# SCH_Arduino-Programmer_2024-08-11.net
KiCad netlist of a schematic drawn in EasyEDA
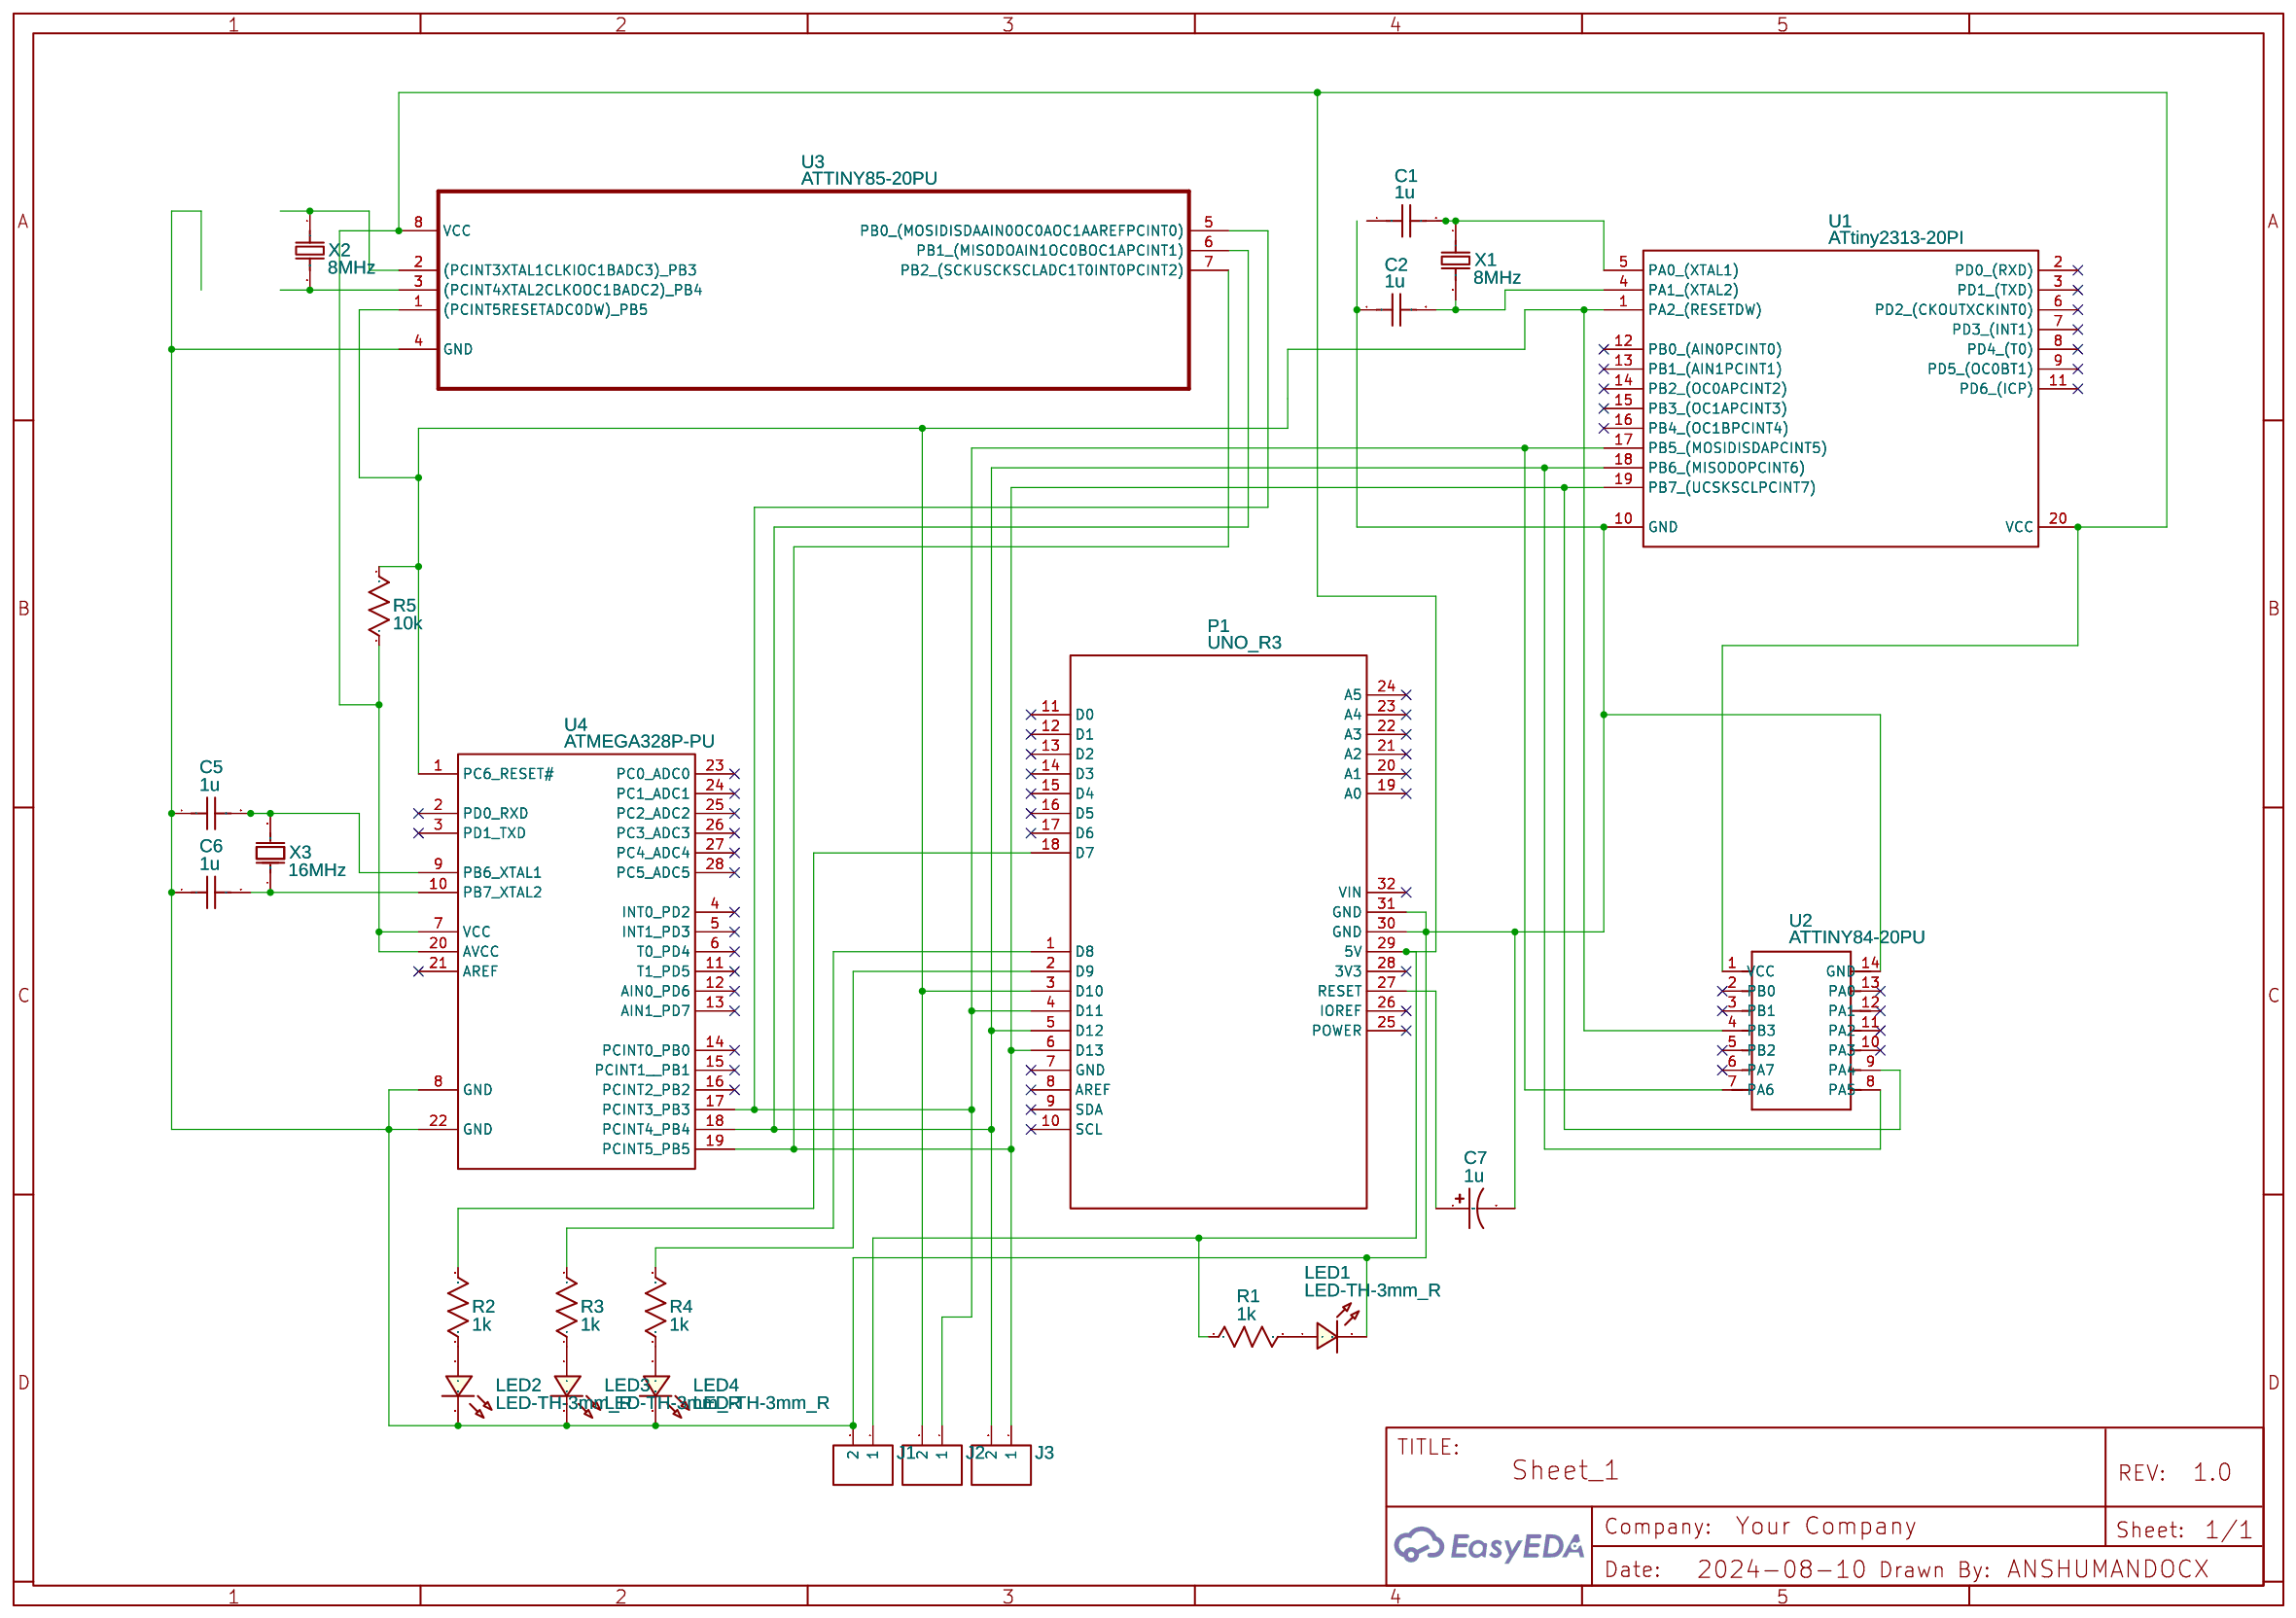
[diagram p0: schematic sheet]

(export (version "E")
  (design (tool "Eeschema 10.0.6"))
  (components
    (comp (ref "C1") (value "1u") (libsource (lib "") (part "C_RAD-0.1_US")))
    (comp (ref "C2") (value "1u") (libsource (lib "") (part "C_RAD-0.1_US")))
    (comp (ref "C5") (value "1u") (libsource (lib "") (part "C_RAD-0.1_US")))
    (comp (ref "C6") (value "1u") (libsource (lib "") (part "C_RAD-0.1_US")))
    (comp (ref "C7") (value "1u") (libsource (lib "") (part "CE_TH_D5.0×F2.0_US")))
    (comp (ref "J1") (value "HDR-M-2.54_1x2") (libsource (lib "") (part "HDR-M-2.54_1x2")))
    (comp (ref "J2") (value "HDR-M-2.54_1x2") (libsource (lib "") (part "HDR-M-2.54_1x2")))
    (comp (ref "J3") (value "HDR-M-2.54_1x2") (libsource (lib "") (part "HDR-M-2.54_1x2")))
    (comp (ref "LED1")
      (value "LED-TH-3mm_R")
      (fields
        (field (name "Manufacturer Part") "204-10SDRD/S530-A3-L")
        (field (name "Manufacturer") "EVERLIGHT(台湾亿光)")
      )
      (libsource (lib "") (part "LED-TH-3mm_R_1"))
    )
    (comp (ref "LED2")
      (value "LED-TH-3mm_R")
      (fields
        (field (name "Manufacturer Part") "204-10SDRD/S530-A3-L")
        (field (name "Manufacturer") "EVERLIGHT(台湾亿光)")
      )
      (libsource (lib "") (part "LED-TH-3mm_R"))
    )
    (comp (ref "LED3")
      (value "LED-TH-3mm_R")
      (fields
        (field (name "Manufacturer Part") "204-10SDRD/S530-A3-L")
        (field (name "Manufacturer") "EVERLIGHT(台湾亿光)")
      )
      (libsource (lib "") (part "LED-TH-3mm_R"))
    )
    (comp (ref "LED4")
      (value "LED-TH-3mm_R")
      (fields
        (field (name "Manufacturer Part") "204-10SDRD/S530-A3-L")
        (field (name "Manufacturer") "EVERLIGHT(台湾亿光)")
      )
      (libsource (lib "") (part "LED-TH-3mm_R"))
    )
    (comp (ref "P1") (value "UNO_R3") (libsource (lib "") (part "UNO_R3")))
    (comp (ref "R1") (value "1k") (libsource (lib "") (part "R_AXIAL-0.4_US")))
    (comp (ref "R2") (value "1k") (libsource (lib "") (part "R_AXIAL-0.4_US_1")))
    (comp (ref "R3") (value "1k") (libsource (lib "") (part "R_AXIAL-0.4_US_1")))
    (comp (ref "R4") (value "1k") (libsource (lib "") (part "R_AXIAL-0.4_US_1")))
    (comp (ref "R5") (value "10k") (libsource (lib "") (part "R_AXIAL-0.4_US_1")))
    (comp (ref "U1") (value "ATtiny2313-20PI") (libsource (lib "") (part "ATtiny2313-20PI")))
    (comp (ref "U2") (value "ATTINY84-20PU") (libsource (lib "") (part "ATTINY84-20PU")))
    (comp (ref "U3") (value "ATTINY85-20PU") (libsource (lib "") (part "ATTINY85-20PU")))
    (comp (ref "U4")
      (value "ATMEGA328P-PU")
      (fields (field (name "Manufacturer") "MICROCHIP(美国微芯)"))
      (libsource (lib "") (part "ATMEGA328P-PU"))
    )
    (comp (ref "X1")
      (value "8MHz")
      (fields (field (name "Manufacturer Part") "9B08000006") (field (name "Manufacturer") "TXC(晶技)"))
      (libsource (lib "") (part "9B0806LCSC-AHQ2S"))
    )
    (comp (ref "X2")
      (value "8MHz")
      (fields (field (name "Manufacturer Part") "9B08000006") (field (name "Manufacturer") "TXC(晶技)"))
      (libsource (lib "") (part "9B0806LCSC-AHQ2S"))
    )
    (comp (ref "X3")
      (value "16MHz")
      (fields
        (field (name "Manufacturer Part") "E49A16E00000DE10C0")
        (field (name "Manufacturer") "HOSONIC(鸿星)")
      )
      (libsource (lib "") (part "E49A16E00000DE10C0"))
    )
  )
  (nets
    (net (code "1") (name "Net-(LED1-Pad1)") (class "Default")
      (node (ref "LED1") (pin "1") (pinfunction "1_1") (pintype "unspecified"))
      (node (ref "R1") (pin "2") (pinfunction "2_2") (pintype "unspecified"))
    )
    (net (code "2") (name "Net-(LED2-Pad1)") (class "Default")
      (node (ref "LED2") (pin "1") (pinfunction "1_1") (pintype "unspecified"))
      (node (ref "R2") (pin "1") (pinfunction "1_1") (pintype "unspecified"))
    )
    (net (code "3") (name "Net-(LED3-Pad1)") (class "Default")
      (node (ref "LED3") (pin "1") (pinfunction "1_1") (pintype "unspecified"))
      (node (ref "R3") (pin "1") (pinfunction "1_1") (pintype "unspecified"))
    )
    (net (code "4") (name "Net-(LED4-Pad1)") (class "Default")
      (node (ref "LED4") (pin "1") (pinfunction "1_1") (pintype "unspecified"))
      (node (ref "R4") (pin "1") (pinfunction "1_1") (pintype "unspecified"))
    )
    (net (code "5") (name "Net-(P1-5V)") (class "Default")
      (node (ref "J1") (pin "1") (pinfunction "1_1") (pintype "unspecified"))
      (node (ref "P1") (pin "29") (pinfunction "5V_29") (pintype "unspecified"))
      (node (ref "R1") (pin "1") (pinfunction "1_1") (pintype "unspecified"))
      (node (ref "R5") (pin "1") (pinfunction "1_1") (pintype "unspecified"))
      (node (ref "U1") (pin "20") (pinfunction "VCC_20") (pintype "passive"))
      (node (ref "U2") (pin "1") (pinfunction "VCC_1") (pintype "unspecified"))
      (node (ref "U3") (pin "8") (pinfunction "VCC_8") (pintype "passive"))
      (node (ref "U4") (pin "20") (pinfunction "AVCC_20") (pintype "passive"))
      (node (ref "U4") (pin "7") (pinfunction "VCC_7") (pintype "passive"))
    )
    (net (code "6") (name "Net-(P1-D7)") (class "Default")
      (node (ref "P1") (pin "18") (pinfunction "D7_18") (pintype "unspecified"))
      (node (ref "R2") (pin "2") (pinfunction "2_2") (pintype "unspecified"))
    )
    (net (code "7") (name "Net-(P1-D8)") (class "Default")
      (node (ref "P1") (pin "1") (pinfunction "D8_1") (pintype "unspecified"))
      (node (ref "R3") (pin "2") (pinfunction "2_2") (pintype "unspecified"))
    )
    (net (code "8") (name "Net-(P1-D9)") (class "Default")
      (node (ref "P1") (pin "2") (pinfunction "D9_2") (pintype "unspecified"))
      (node (ref "R4") (pin "2") (pinfunction "2_2") (pintype "unspecified"))
    )
    (net (code "9") (name "Net-(P1-D10)") (class "Default")
      (node (ref "J2") (pin "2") (pinfunction "2_2") (pintype "unspecified"))
      (node (ref "P1") (pin "3") (pinfunction "D10_3") (pintype "unspecified"))
      (node (ref "R5") (pin "2") (pinfunction "2_2") (pintype "unspecified"))
      (node (ref "U1") (pin "1") (pinfunction "PA2_(RESETDW)_1") (pintype "bidirectional"))
      (node (ref "U2") (pin "4") (pinfunction "PB3_4") (pintype "unspecified"))
      (node (ref "U3") (pin "1") (pinfunction "(PCINT5RESETADC0DW)_PB5_1") (pintype "unspecified"))
      (node (ref "U4") (pin "1") (pinfunction "PC6_RESET#_1") (pintype "bidirectional"))
    )
    (net (code "10") (name "Net-(P1-D11)") (class "Default")
      (node (ref "J2") (pin "1") (pinfunction "1_1") (pintype "unspecified"))
      (node (ref "P1") (pin "4") (pinfunction "D11_4") (pintype "unspecified"))
      (node (ref "U1") (pin "17") (pinfunction "PB5_(MOSIDISDAPCINT5)_17") (pintype "bidirectional"))
      (node (ref "U2") (pin "7") (pinfunction "PA6_7") (pintype "unspecified"))
      (node (ref "U3") (pin "5") (pinfunction "PB0_(MOSIDISDAAIN0OC0AOC1AAREFPCINT0)_5") (pintype "unspecified"))
      (node (ref "U4") (pin "17") (pinfunction "PCINT3_PB3_17") (pintype "bidirectional"))
    )
    (net (code "11") (name "Net-(P1-D12)") (class "Default")
      (node (ref "J3") (pin "2") (pinfunction "2_2") (pintype "unspecified"))
      (node (ref "P1") (pin "5") (pinfunction "D12_5") (pintype "unspecified"))
      (node (ref "U1") (pin "18") (pinfunction "PB6_(MISODOPCINT6)_18") (pintype "bidirectional"))
      (node (ref "U2") (pin "8") (pinfunction "PA5_8") (pintype "unspecified"))
      (node (ref "U3") (pin "6") (pinfunction "PB1_(MISODOAIN1OC0BOC1APCINT1)_6") (pintype "unspecified"))
      (node (ref "U4") (pin "18") (pinfunction "PCINT4_PB4_18") (pintype "bidirectional"))
    )
    (net (code "12") (name "Net-(P1-D13)") (class "Default")
      (node (ref "J3") (pin "1") (pinfunction "1_1") (pintype "unspecified"))
      (node (ref "P1") (pin "6") (pinfunction "D13_6") (pintype "unspecified"))
      (node (ref "U1") (pin "19") (pinfunction "PB7_(UCSKSCLPCINT7)_19") (pintype "bidirectional"))
      (node (ref "U2") (pin "9") (pinfunction "PA4_9") (pintype "unspecified"))
      (node (ref "U3") (pin "7") (pinfunction "PB2_(SCKUSCKSCLADC1T0INT0PCINT2)_7") (pintype "unspecified"))
      (node (ref "U4") (pin "19") (pinfunction "PCINT5_PB5_19") (pintype "bidirectional"))
    )
    (net (code "13") (name "Net-(P1-RESET)") (class "Default")
      (node (ref "C7") (pin "1") (pinfunction "1_1") (pintype "unspecified"))
      (node (ref "P1") (pin "27") (pinfunction "RESET_27") (pintype "unspecified"))
    )
    (net (code "14") (name "Net-(U1-GND)") (class "Default")
      (node (ref "C2") (pin "1") (pinfunction "1_1") (pintype "unspecified"))
      (node (ref "C5") (pin "1") (pinfunction "1_1") (pintype "unspecified"))
      (node (ref "C6") (pin "1") (pinfunction "1_1") (pintype "unspecified"))
      (node (ref "C7") (pin "2") (pinfunction "2_2") (pintype "unspecified"))
      (node (ref "J1") (pin "2") (pinfunction "2_2") (pintype "unspecified"))
      (node (ref "LED1") (pin "2") (pinfunction "2_2") (pintype "unspecified"))
      (node (ref "LED2") (pin "2") (pinfunction "2_2") (pintype "unspecified"))
      (node (ref "LED3") (pin "2") (pinfunction "2_2") (pintype "unspecified"))
      (node (ref "LED4") (pin "2") (pinfunction "2_2") (pintype "unspecified"))
      (node (ref "P1") (pin "30") (pinfunction "GND_30") (pintype "unspecified"))
      (node (ref "P1") (pin "31") (pinfunction "GND_31") (pintype "unspecified"))
      (node (ref "U1") (pin "10") (pinfunction "GND_10") (pintype "passive"))
      (node (ref "U2") (pin "14") (pinfunction "GND_14") (pintype "unspecified"))
      (node (ref "U3") (pin "4") (pinfunction "GND_4") (pintype "unspecified"))
      (node (ref "U4") (pin "22") (pinfunction "GND_22") (pintype "passive"))
      (node (ref "U4") (pin "8") (pinfunction "GND_8") (pintype "passive"))
    )
    (net (code "15") (name "Net-(U1-PA0_(XTAL1))") (class "Default")
      (node (ref "C1") (pin "2") (pinfunction "2_2") (pintype "unspecified"))
      (node (ref "U1") (pin "5") (pinfunction "PA0_(XTAL1)_5") (pintype "bidirectional"))
      (node (ref "X1") (pin "1") (pinfunction "1_1") (pintype "unspecified"))
    )
    (net (code "16") (name "Net-(U1-PA1_(XTAL2))") (class "Default")
      (node (ref "C2") (pin "2") (pinfunction "2_2") (pintype "unspecified"))
      (node (ref "U1") (pin "4") (pinfunction "PA1_(XTAL2)_4") (pintype "bidirectional"))
      (node (ref "X1") (pin "2") (pinfunction "2_2") (pintype "unspecified"))
    )
    (net (code "17") (name "Net-(U3-(PCINT3XTAL1CLKIOC1BADC3)_PB3)") (class "Default")
      (node (ref "U3") (pin "2") (pinfunction "(PCINT3XTAL1CLKIOC1BADC3)_PB3_2") (pintype "unspecified"))
      (node (ref "X2") (pin "1") (pinfunction "1_1") (pintype "unspecified"))
    )
    (net (code "18") (name "Net-(U3-(PCINT4XTAL2CLKOOC1BADC2)_PB4)") (class "Default")
      (node (ref "U3") (pin "3") (pinfunction "(PCINT4XTAL2CLKOOC1BADC2)_PB4_3") (pintype "unspecified"))
      (node (ref "X2") (pin "2") (pinfunction "2_2") (pintype "unspecified"))
    )
    (net (code "19") (name "Net-(U4-PB6_XTAL1)") (class "Default")
      (node (ref "C5") (pin "2") (pinfunction "2_2") (pintype "unspecified"))
      (node (ref "U4") (pin "9") (pinfunction "PB6_XTAL1_9") (pintype "bidirectional"))
      (node (ref "X3") (pin "2") (pinfunction "OSC2_2") (pintype "input"))
    )
    (net (code "20") (name "Net-(U4-PB7_XTAL2)") (class "Default")
      (node (ref "C6") (pin "2") (pinfunction "2_2") (pintype "unspecified"))
      (node (ref "U4") (pin "10") (pinfunction "PB7_XTAL2_10") (pintype "bidirectional"))
      (node (ref "X3") (pin "1") (pinfunction "OSC1_1") (pintype "input"))
    )
    (net (code "21") (name "unconnected-(C1-Pad1)") (class "Default")
      (node (ref "C1") (pin "1") (pinfunction "1_1") (pintype "unspecified"))
    )
    (net (code "22") (name "unconnected-(P1-3V3-Pad28)") (class "Default")
      (node (ref "P1") (pin "28") (pinfunction "3V3_28") (pintype "unspecified+no_connect"))
    )
    (net (code "23") (name "unconnected-(P1-A0-Pad19)") (class "Default")
      (node (ref "P1") (pin "19") (pinfunction "A0_19") (pintype "unspecified+no_connect"))
    )
    (net (code "24") (name "unconnected-(P1-A1-Pad20)") (class "Default")
      (node (ref "P1") (pin "20") (pinfunction "A1_20") (pintype "unspecified+no_connect"))
    )
    (net (code "25") (name "unconnected-(P1-A2-Pad21)") (class "Default")
      (node (ref "P1") (pin "21") (pinfunction "A2_21") (pintype "unspecified+no_connect"))
    )
    (net (code "26") (name "unconnected-(P1-A3-Pad22)") (class "Default")
      (node (ref "P1") (pin "22") (pinfunction "A3_22") (pintype "unspecified+no_connect"))
    )
    (net (code "27") (name "unconnected-(P1-A4-Pad23)") (class "Default")
      (node (ref "P1") (pin "23") (pinfunction "A4_23") (pintype "unspecified+no_connect"))
    )
    (net (code "28") (name "unconnected-(P1-A5-Pad24)") (class "Default")
      (node (ref "P1") (pin "24") (pinfunction "A5_24") (pintype "unspecified+no_connect"))
    )
    (net (code "29") (name "unconnected-(P1-AREF-Pad8)") (class "Default")
      (node (ref "P1") (pin "8") (pinfunction "AREF_8") (pintype "unspecified+no_connect"))
    )
    (net (code "30") (name "unconnected-(P1-D0-Pad11)") (class "Default")
      (node (ref "P1") (pin "11") (pinfunction "D0_11") (pintype "unspecified+no_connect"))
    )
    (net (code "31") (name "unconnected-(P1-D1-Pad12)") (class "Default")
      (node (ref "P1") (pin "12") (pinfunction "D1_12") (pintype "unspecified+no_connect"))
    )
    (net (code "32") (name "unconnected-(P1-D2-Pad13)") (class "Default")
      (node (ref "P1") (pin "13") (pinfunction "D2_13") (pintype "unspecified+no_connect"))
    )
    (net (code "33") (name "unconnected-(P1-D3-Pad14)") (class "Default")
      (node (ref "P1") (pin "14") (pinfunction "D3_14") (pintype "unspecified+no_connect"))
    )
    (net (code "34") (name "unconnected-(P1-D4-Pad15)") (class "Default")
      (node (ref "P1") (pin "15") (pinfunction "D4_15") (pintype "unspecified+no_connect"))
    )
    (net (code "35") (name "unconnected-(P1-D5-Pad16)") (class "Default")
      (node (ref "P1") (pin "16") (pinfunction "D5_16") (pintype "unspecified+no_connect"))
    )
    (net (code "36") (name "unconnected-(P1-D6-Pad17)") (class "Default")
      (node (ref "P1") (pin "17") (pinfunction "D6_17") (pintype "unspecified+no_connect"))
    )
    (net (code "37") (name "unconnected-(P1-GND-Pad7)") (class "Default")
      (node (ref "P1") (pin "7") (pinfunction "GND_7") (pintype "unspecified+no_connect"))
    )
    (net (code "38") (name "unconnected-(P1-IOREF-Pad26)") (class "Default")
      (node (ref "P1") (pin "26") (pinfunction "IOREF_26") (pintype "unspecified+no_connect"))
    )
    (net (code "39") (name "unconnected-(P1-POWER-Pad25)") (class "Default")
      (node (ref "P1") (pin "25") (pinfunction "POWER_25") (pintype "unspecified+no_connect"))
    )
    (net (code "40") (name "unconnected-(P1-SCL-Pad10)") (class "Default")
      (node (ref "P1") (pin "10") (pinfunction "SCL_10") (pintype "unspecified+no_connect"))
    )
    (net (code "41") (name "unconnected-(P1-SDA-Pad9)") (class "Default")
      (node (ref "P1") (pin "9") (pinfunction "SDA_9") (pintype "unspecified+no_connect"))
    )
    (net (code "42") (name "unconnected-(P1-VIN-Pad32)") (class "Default")
      (node (ref "P1") (pin "32") (pinfunction "VIN_32") (pintype "unspecified+no_connect"))
    )
    (net (code "43") (name "unconnected-(U1-PB0_(AIN0PCINT0)-Pad12)") (class "Default")
      (node (ref "U1") (pin "12") (pinfunction "PB0_(AIN0PCINT0)_12") (pintype "bidirectional+no_connect"))
    )
    (net (code "44") (name "unconnected-(U1-PB1_(AIN1PCINT1)-Pad13)") (class "Default")
      (node (ref "U1") (pin "13") (pinfunction "PB1_(AIN1PCINT1)_13") (pintype "bidirectional+no_connect"))
    )
    (net (code "45") (name "unconnected-(U1-PB2_(OC0APCINT2)-Pad14)") (class "Default")
      (node (ref "U1") (pin "14") (pinfunction "PB2_(OC0APCINT2)_14") (pintype "bidirectional+no_connect"))
    )
    (net (code "46") (name "unconnected-(U1-PB3_(OC1APCINT3)-Pad15)") (class "Default")
      (node (ref "U1") (pin "15") (pinfunction "PB3_(OC1APCINT3)_15") (pintype "bidirectional+no_connect"))
    )
    (net (code "47") (name "unconnected-(U1-PB4_(OC1BPCINT4)-Pad16)") (class "Default")
      (node (ref "U1") (pin "16") (pinfunction "PB4_(OC1BPCINT4)_16") (pintype "bidirectional+no_connect"))
    )
    (net (code "48") (name "unconnected-(U1-PD0_(RXD)-Pad2)") (class "Default")
      (node (ref "U1") (pin "2") (pinfunction "PD0_(RXD)_2") (pintype "bidirectional+no_connect"))
    )
    (net (code "49") (name "unconnected-(U1-PD1_(TXD)-Pad3)") (class "Default")
      (node (ref "U1") (pin "3") (pinfunction "PD1_(TXD)_3") (pintype "bidirectional+no_connect"))
    )
    (net (code "50") (name "unconnected-(U1-PD2_(CKOUTXCKINT0)-Pad6)") (class "Default")
      (node (ref "U1") (pin "6") (pinfunction "PD2_(CKOUTXCKINT0)_6") (pintype "bidirectional+no_connect"))
    )
    (net (code "51") (name "unconnected-(U1-PD3_(INT1)-Pad7)") (class "Default")
      (node (ref "U1") (pin "7") (pinfunction "PD3_(INT1)_7") (pintype "bidirectional+no_connect"))
    )
    (net (code "52") (name "unconnected-(U1-PD4_(T0)-Pad8)") (class "Default")
      (node (ref "U1") (pin "8") (pinfunction "PD4_(T0)_8") (pintype "bidirectional+no_connect"))
    )
    (net (code "53") (name "unconnected-(U1-PD5_(OC0BT1)-Pad9)") (class "Default")
      (node (ref "U1") (pin "9") (pinfunction "PD5_(OC0BT1)_9") (pintype "bidirectional+no_connect"))
    )
    (net (code "54") (name "unconnected-(U1-PD6_(ICP)-Pad11)") (class "Default")
      (node (ref "U1") (pin "11") (pinfunction "PD6_(ICP)_11") (pintype "bidirectional+no_connect"))
    )
    (net (code "55") (name "unconnected-(U2-PA0-Pad13)") (class "Default")
      (node (ref "U2") (pin "13") (pinfunction "PA0_13") (pintype "unspecified+no_connect"))
    )
    (net (code "56") (name "unconnected-(U2-PA1-Pad12)") (class "Default")
      (node (ref "U2") (pin "12") (pinfunction "PA1_12") (pintype "unspecified+no_connect"))
    )
    (net (code "57") (name "unconnected-(U2-PA2-Pad11)") (class "Default")
      (node (ref "U2") (pin "11") (pinfunction "PA2_11") (pintype "unspecified+no_connect"))
    )
    (net (code "58") (name "unconnected-(U2-PA3-Pad10)") (class "Default")
      (node (ref "U2") (pin "10") (pinfunction "PA3_10") (pintype "unspecified+no_connect"))
    )
    (net (code "59") (name "unconnected-(U2-PA7-Pad6)") (class "Default")
      (node (ref "U2") (pin "6") (pinfunction "PA7_6") (pintype "unspecified+no_connect"))
    )
    (net (code "60") (name "unconnected-(U2-PB0-Pad2)") (class "Default")
      (node (ref "U2") (pin "2") (pinfunction "PB0_2") (pintype "unspecified+no_connect"))
    )
    (net (code "61") (name "unconnected-(U2-PB1-Pad3)") (class "Default")
      (node (ref "U2") (pin "3") (pinfunction "PB1_3") (pintype "unspecified+no_connect"))
    )
    (net (code "62") (name "unconnected-(U2-PB2-Pad5)") (class "Default")
      (node (ref "U2") (pin "5") (pinfunction "PB2_5") (pintype "unspecified+no_connect"))
    )
    (net (code "63") (name "unconnected-(U4-AIN0_PD6-Pad12)") (class "Default")
      (node (ref "U4") (pin "12") (pinfunction "AIN0_PD6_12") (pintype "bidirectional+no_connect"))
    )
    (net (code "64") (name "unconnected-(U4-AIN1_PD7-Pad13)") (class "Default")
      (node (ref "U4") (pin "13") (pinfunction "AIN1_PD7_13") (pintype "bidirectional+no_connect"))
    )
    (net (code "65") (name "unconnected-(U4-AREF-Pad21)") (class "Default")
      (node (ref "U4") (pin "21") (pinfunction "AREF_21") (pintype "passive+no_connect"))
    )
    (net (code "66") (name "unconnected-(U4-INT0_PD2-Pad4)") (class "Default")
      (node (ref "U4") (pin "4") (pinfunction "INT0_PD2_4") (pintype "bidirectional+no_connect"))
    )
    (net (code "67") (name "unconnected-(U4-INT1_PD3-Pad5)") (class "Default")
      (node (ref "U4") (pin "5") (pinfunction "INT1_PD3_5") (pintype "bidirectional+no_connect"))
    )
    (net (code "68") (name "unconnected-(U4-PC0_ADC0-Pad23)") (class "Default")
      (node (ref "U4") (pin "23") (pinfunction "PC0_ADC0_23") (pintype "bidirectional+no_connect"))
    )
    (net (code "69") (name "unconnected-(U4-PC1_ADC1-Pad24)") (class "Default")
      (node (ref "U4") (pin "24") (pinfunction "PC1_ADC1_24") (pintype "bidirectional+no_connect"))
    )
    (net (code "70") (name "unconnected-(U4-PC2_ADC2-Pad25)") (class "Default")
      (node (ref "U4") (pin "25") (pinfunction "PC2_ADC2_25") (pintype "bidirectional+no_connect"))
    )
    (net (code "71") (name "unconnected-(U4-PC3_ADC3-Pad26)") (class "Default")
      (node (ref "U4") (pin "26") (pinfunction "PC3_ADC3_26") (pintype "bidirectional+no_connect"))
    )
    (net (code "72") (name "unconnected-(U4-PC4_ADC4-Pad27)") (class "Default")
      (node (ref "U4") (pin "27") (pinfunction "PC4_ADC4_27") (pintype "bidirectional+no_connect"))
    )
    (net (code "73") (name "unconnected-(U4-PC5_ADC5-Pad28)") (class "Default")
      (node (ref "U4") (pin "28") (pinfunction "PC5_ADC5_28") (pintype "bidirectional+no_connect"))
    )
    (net (code "74") (name "unconnected-(U4-PCINT0_PB0-Pad14)") (class "Default")
      (node (ref "U4") (pin "14") (pinfunction "PCINT0_PB0_14") (pintype "bidirectional+no_connect"))
    )
    (net (code "75") (name "unconnected-(U4-PCINT1__PB1-Pad15)") (class "Default")
      (node (ref "U4") (pin "15") (pinfunction "PCINT1__PB1_15") (pintype "bidirectional+no_connect"))
    )
    (net (code "76") (name "unconnected-(U4-PCINT2_PB2-Pad16)") (class "Default")
      (node (ref "U4") (pin "16") (pinfunction "PCINT2_PB2_16") (pintype "bidirectional+no_connect"))
    )
    (net (code "77") (name "unconnected-(U4-PD0_RXD-Pad2)") (class "Default")
      (node (ref "U4") (pin "2") (pinfunction "PD0_RXD_2") (pintype "bidirectional+no_connect"))
    )
    (net (code "78") (name "unconnected-(U4-PD1_TXD-Pad3)") (class "Default")
      (node (ref "U4") (pin "3") (pinfunction "PD1_TXD_3") (pintype "bidirectional+no_connect"))
    )
    (net (code "79") (name "unconnected-(U4-T0_PD4-Pad6)") (class "Default")
      (node (ref "U4") (pin "6") (pinfunction "T0_PD4_6") (pintype "bidirectional+no_connect"))
    )
    (net (code "80") (name "unconnected-(U4-T1_PD5-Pad11)") (class "Default")
      (node (ref "U4") (pin "11") (pinfunction "T1_PD5_11") (pintype "bidirectional+no_connect"))
    )
  )
)
